# Temp.net
KiCad netlist of a schematic drawn in Altium Designer
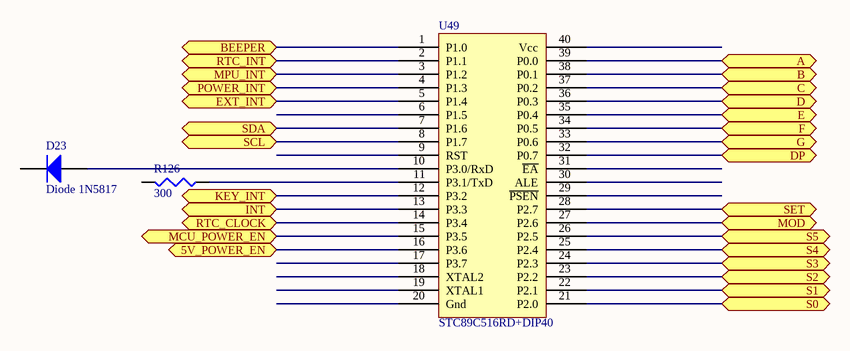
[diagram p0: Temp.SchDoc]

(export (version "E")
  (design (tool "Eeschema 10.0.6"))
  (components
    (comp (ref "D23")
      (value "Diode 1N5817")
      (footprint "clock:SMA")
      (description "1 Amp General Purpose Rectifier")
      (fields (field (name "PUBLISHER") "Altium Limited"))
      (libsource (lib "Miscellaneous Devices") (part "Diode 1N4005"))
    )
    (comp (ref "R126")
      (value "300")
      (footprint "clock:0603")
      (description "Resistor")
      (fields (field (name "Comment") "Res3") (field (name "PUBLISHER") "Altium Limited"))
      (libsource (lib "Miscellaneous Devices") (part "Res3"))
    )
    (comp (ref "U49") (value "STC89C516RD+DIP40") (libsource (lib "clock") (part "STC89C516RD+DIP40")))
  )
  (nets
    (net (code "1") (name "/5V_POWER_EN") (class "Default")
      (node (ref "U49") (pin "16") (pinfunction "P3.6_16") (pintype "passive"))
    )
    (net (code "2") (name "/A") (class "Default")
      (node (ref "U49") (pin "39") (pinfunction "P0.0_39") (pintype "passive"))
    )
    (net (code "3") (name "/B") (class "Default")
      (node (ref "U49") (pin "38") (pinfunction "P0.1_38") (pintype "passive"))
    )
    (net (code "4") (name "/BEEPER") (class "Default")
      (node (ref "U49") (pin "1") (pinfunction "P1.0_1") (pintype "passive"))
    )
    (net (code "5") (name "/C") (class "Default")
      (node (ref "U49") (pin "37") (pinfunction "P0.2_37") (pintype "passive"))
    )
    (net (code "6") (name "/D") (class "Default")
      (node (ref "U49") (pin "36") (pinfunction "P0.3_36") (pintype "passive"))
    )
    (net (code "7") (name "/DP") (class "Default")
      (node (ref "U49") (pin "32") (pinfunction "P0.7_32") (pintype "passive"))
    )
    (net (code "8") (name "/E") (class "Default")
      (node (ref "U49") (pin "35") (pinfunction "P0.4_35") (pintype "passive"))
    )
    (net (code "9") (name "/EXT_INT") (class "Default")
      (node (ref "U49") (pin "5") (pinfunction "P1.4_5") (pintype "passive"))
    )
    (net (code "10") (name "/F") (class "Default")
      (node (ref "U49") (pin "34") (pinfunction "P0.5_34") (pintype "passive"))
    )
    (net (code "11") (name "/G") (class "Default")
      (node (ref "U49") (pin "33") (pinfunction "P0.6_33") (pintype "passive"))
    )
    (net (code "12") (name "/INT") (class "Default")
      (node (ref "U49") (pin "13") (pinfunction "P3.3_13") (pintype "passive"))
    )
    (net (code "13") (name "/KEY_INT") (class "Default")
      (node (ref "U49") (pin "12") (pinfunction "P3.2_12") (pintype "passive"))
    )
    (net (code "14") (name "/MCU_POWER_EN") (class "Default")
      (node (ref "U49") (pin "15") (pinfunction "P3.5_15") (pintype "passive"))
    )
    (net (code "15") (name "/MOD") (class "Default")
      (node (ref "U49") (pin "27") (pinfunction "P2.6_27") (pintype "passive"))
    )
    (net (code "16") (name "/MPU_INT") (class "Default")
      (node (ref "U49") (pin "3") (pinfunction "P1.2_3") (pintype "passive"))
    )
    (net (code "17") (name "/POWER_INT") (class "Default")
      (node (ref "U49") (pin "4") (pinfunction "P1.3_4") (pintype "passive"))
    )
    (net (code "18") (name "/RTC_CLOCK") (class "Default")
      (node (ref "U49") (pin "14") (pinfunction "P3.4_14") (pintype "passive"))
    )
    (net (code "19") (name "/RTC_INT") (class "Default")
      (node (ref "U49") (pin "2") (pinfunction "P1.1_2") (pintype "passive"))
    )
    (net (code "20") (name "/S0") (class "Default")
      (node (ref "U49") (pin "21") (pinfunction "P2.0_21") (pintype "passive"))
    )
    (net (code "21") (name "/S1") (class "Default")
      (node (ref "U49") (pin "22") (pinfunction "P2.1_22") (pintype "passive"))
    )
    (net (code "22") (name "/S2") (class "Default")
      (node (ref "U49") (pin "23") (pinfunction "P2.2_23") (pintype "passive"))
    )
    (net (code "23") (name "/S3") (class "Default")
      (node (ref "U49") (pin "24") (pinfunction "P2.3_24") (pintype "passive"))
    )
    (net (code "24") (name "/S4") (class "Default")
      (node (ref "U49") (pin "25") (pinfunction "P2.4_25") (pintype "passive"))
    )
    (net (code "25") (name "/S5") (class "Default")
      (node (ref "U49") (pin "26") (pinfunction "P2.5_26") (pintype "passive"))
    )
    (net (code "26") (name "/SCL") (class "Default")
      (node (ref "U49") (pin "8") (pinfunction "P1.7_8") (pintype "passive"))
    )
    (net (code "27") (name "/SDA") (class "Default")
      (node (ref "U49") (pin "7") (pinfunction "P1.6_7") (pintype "passive"))
    )
    (net (code "28") (name "/SET") (class "Default")
      (node (ref "U49") (pin "28") (pinfunction "P2.7_28") (pintype "passive"))
    )
    (net (code "29") (name "Net-(D23-A)") (class "Default")
      (node (ref "D23") (pin "1") (pinfunction "A_1") (pintype "passive"))
      (node (ref "U49") (pin "10") (pinfunction "P3.0/RxD_10") (pintype "passive"))
    )
    (net (code "30") (name "Net-(U49-P3.1{slash}TxD)") (class "Default")
      (node (ref "R126") (pin "1") (pinfunction "1_1") (pintype "passive"))
      (node (ref "U49") (pin "11") (pinfunction "P3.1/TxD_11") (pintype "passive"))
    )
    (net (code "31") (name "unconnected-(D23-K-Pad2)") (class "Default")
      (node (ref "D23") (pin "2") (pinfunction "K_2") (pintype "passive"))
    )
    (net (code "32") (name "unconnected-(R126-Pad2)") (class "Default")
      (node (ref "R126") (pin "2") (pinfunction "2_2") (pintype "passive"))
    )
    (net (code "33") (name "unconnected-(U49-ALE-Pad30)") (class "Default")
      (node (ref "U49") (pin "30") (pinfunction "ALE_30") (pintype "passive"))
    )
    (net (code "34") (name "unconnected-(U49-Gnd-Pad20)") (class "Default")
      (node (ref "U49") (pin "20") (pinfunction "Gnd_20") (pintype "passive"))
    )
    (net (code "35") (name "unconnected-(U49-P1.5-Pad6)") (class "Default")
      (node (ref "U49") (pin "6") (pinfunction "P1.5_6") (pintype "passive"))
    )
    (net (code "36") (name "unconnected-(U49-P3.7-Pad17)") (class "Default")
      (node (ref "U49") (pin "17") (pinfunction "P3.7_17") (pintype "passive"))
    )
    (net (code "37") (name "unconnected-(U49-RST-Pad9)") (class "Default")
      (node (ref "U49") (pin "9") (pinfunction "RST_9") (pintype "passive"))
    )
    (net (code "38") (name "unconnected-(U49-Vcc-Pad40)") (class "Default")
      (node (ref "U49") (pin "40") (pinfunction "Vcc_40") (pintype "passive"))
    )
    (net (code "39") (name "unconnected-(U49-XTAL1-Pad19)") (class "Default")
      (node (ref "U49") (pin "19") (pinfunction "XTAL1_19") (pintype "passive"))
    )
    (net (code "40") (name "unconnected-(U49-XTAL2-Pad18)") (class "Default")
      (node (ref "U49") (pin "18") (pinfunction "XTAL2_18") (pintype "passive"))
    )
    (net (code "41") (name "unconnected-(U49-~{EA}-Pad31)") (class "Default")
      (node (ref "U49") (pin "31") (pinfunction "~{EA}_31") (pintype "passive"))
    )
    (net (code "42") (name "unconnected-(U49-~{PSEN}-Pad29)") (class "Default")
      (node (ref "U49") (pin "29") (pinfunction "~{PSEN}_29") (pintype "passive"))
    )
  )
)
